# imu_mk1.net
KiCad netlist of a schematic drawn in EAGLE
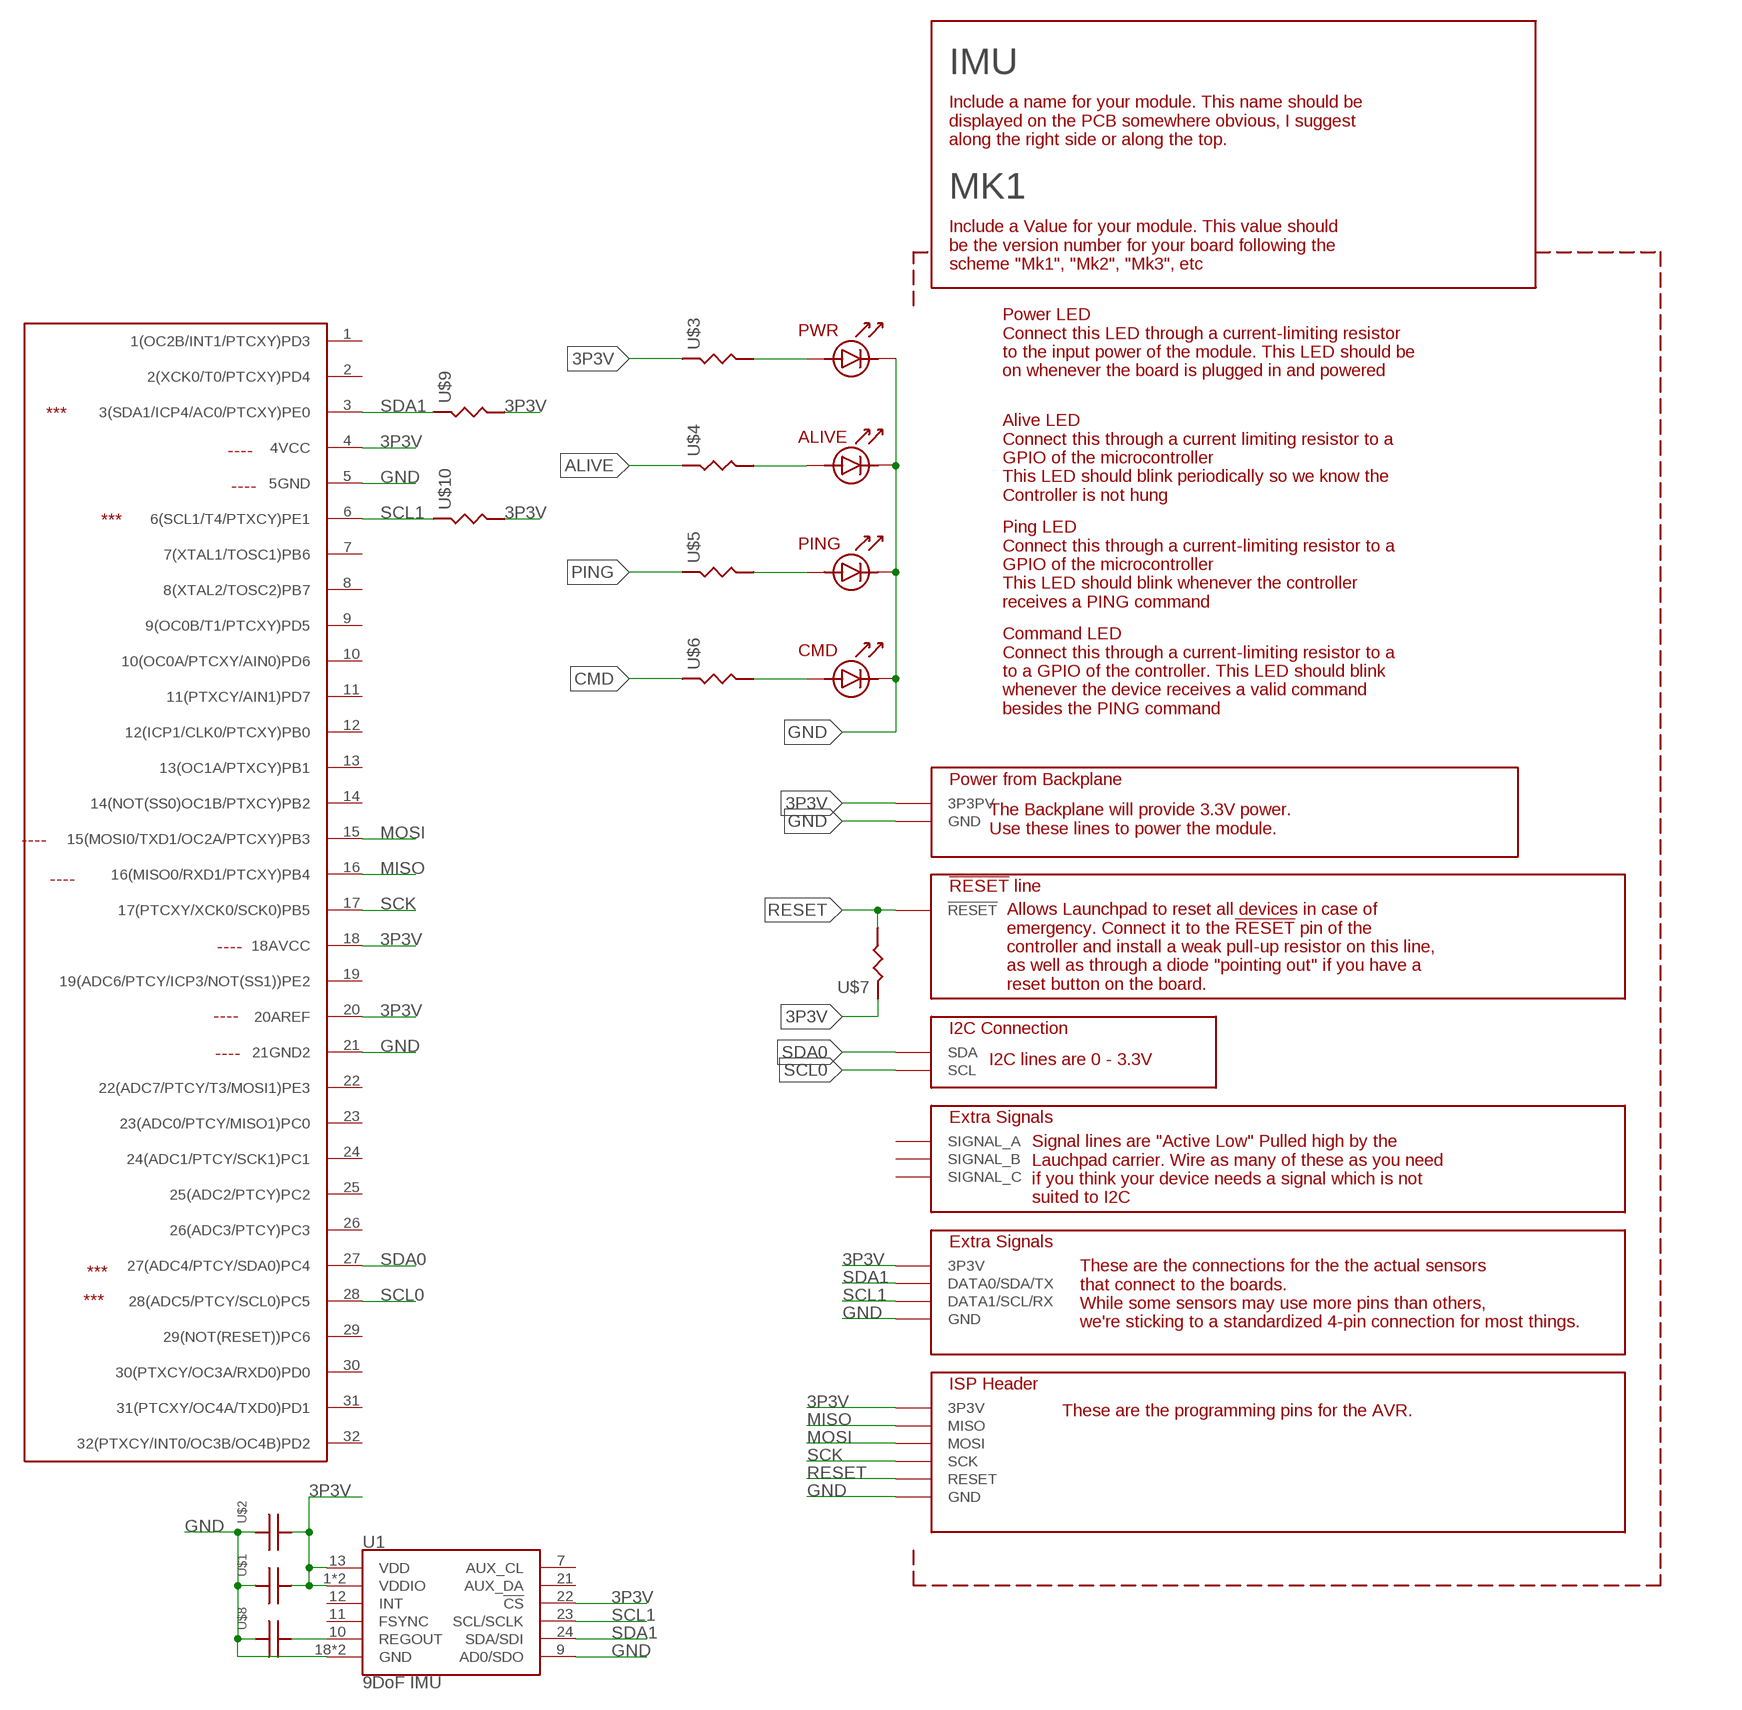
[diagram p0: schematic, sheet 1]

(export (version "E")
  (design (tool "Eeschema 10.0.6"))
  (components
    (comp (ref "IMU")
      (value "MK1")
      (footprint "eagle-import:SENSOR_MODULE_MK1")
      (libsource (lib "eagle-import") (part "SENSOR_MODULE_MK1"))
    )
    (comp (ref "U$1")
      (value "CAPACITOR-UNPOLARIZED0805")
      (footprint "eagle-import:0805_STACKPOLERESISTOR")
      (libsource (lib "eagle-import") (part "CAPACITOR-UNPOLARIZED0805"))
    )
    (comp (ref "U$2")
      (value "CAPACITOR-UNPOLARIZED0805")
      (footprint "eagle-import:0805_STACKPOLERESISTOR")
      (libsource (lib "eagle-import") (part "CAPACITOR-UNPOLARIZED0805"))
    )
    (comp (ref "U$3")
      (value "RESISTOR")
      (footprint "eagle-import:0805_STACKPOLERESISTOR")
      (libsource (lib "eagle-import") (part "RESISTOR"))
    )
    (comp (ref "U$4")
      (value "RESISTOR")
      (footprint "eagle-import:0805_STACKPOLERESISTOR")
      (libsource (lib "eagle-import") (part "RESISTOR"))
    )
    (comp (ref "U$5")
      (value "RESISTOR")
      (footprint "eagle-import:0805_STACKPOLERESISTOR")
      (libsource (lib "eagle-import") (part "RESISTOR"))
    )
    (comp (ref "U$6")
      (value "RESISTOR")
      (footprint "eagle-import:0805_STACKPOLERESISTOR")
      (libsource (lib "eagle-import") (part "RESISTOR"))
    )
    (comp (ref "U$7")
      (value "RESISTOR")
      (footprint "eagle-import:0805_STACKPOLERESISTOR")
      (libsource (lib "eagle-import") (part "RESISTOR"))
    )
    (comp (ref "U$8")
      (value "CAPACITOR-UNPOLARIZED0805")
      (footprint "eagle-import:0805_STACKPOLERESISTOR")
      (libsource (lib "eagle-import") (part "CAPACITOR-UNPOLARIZED0805"))
    )
    (comp (ref "U$9")
      (value "RESISTOR")
      (footprint "eagle-import:0805_STACKPOLERESISTOR")
      (libsource (lib "eagle-import") (part "RESISTOR"))
    )
    (comp (ref "U$10")
      (value "RESISTOR")
      (footprint "eagle-import:0805_STACKPOLERESISTOR")
      (libsource (lib "eagle-import") (part "RESISTOR"))
    )
    (comp (ref "U1")
      (value "9DoF IMU")
      (footprint "eagle-import:QFN24-3X3")
      (libsource (lib "eagle-import") (part "MPU-9250"))
    )
    (comp (ref "U100")
      (value "ATMEGA328PB")
      (footprint "eagle-import:TQFP32-08")
      (libsource (lib "eagle-import") (part "ATMEGA328PB"))
    )
  )
  (nets
    (net (code "1") (name "/MISO") (class "Default")
      (node (ref "IMU") (pin "MISO") (pinfunction "MISO_MISO") (pintype "bidirectional"))
      (node (ref "U100") (pin "16") (pinfunction "16(MISO0/RXD1/PTCXY)PB4_16") (pintype "bidirectional"))
    )
    (net (code "2") (name "/MOSI") (class "Default")
      (node (ref "IMU") (pin "MOSI") (pinfunction "MOSI_MOSI") (pintype "bidirectional"))
      (node (ref "U100") (pin "15") (pinfunction "15(MOSI0/TXD1/OC2A/PTCXY)PB3_15") (pintype "bidirectional"))
    )
    (net (code "3") (name "/SCK") (class "Default")
      (node (ref "IMU") (pin "SCK") (pinfunction "SCK_SCK") (pintype "bidirectional"))
      (node (ref "U100") (pin "17") (pinfunction "17(PTCXY/XCK0/SCK0)PB5_17") (pintype "bidirectional"))
    )
    (net (code "4") (name "/SCL1") (class "Default")
      (node (ref "IMU") (pin "DATA1@1") (pinfunction "DATA1/SCL/RX_DATA1@1") (pintype "bidirectional"))
      (node (ref "IMU") (pin "DATA1@2") (pinfunction "DATA1/SCL/RX_DATA1@2") (pintype "bidirectional"))
      (node (ref "U$10") (pin "P$1") (pinfunction "P$1_P$1") (pintype "bidirectional"))
      (node (ref "U1") (pin "23") (pinfunction "SCL/SCLK_23") (pintype "bidirectional"))
      (node (ref "U100") (pin "6") (pinfunction "6(SCL1/T4/PTXCY)PE1_6") (pintype "bidirectional"))
    )
    (net (code "5") (name "/SDA1") (class "Default")
      (node (ref "IMU") (pin "DATA0@1") (pinfunction "DATA0/SDA/TX_DATA0@1") (pintype "bidirectional"))
      (node (ref "IMU") (pin "DATA0@2") (pinfunction "DATA0/SDA/TX_DATA0@2") (pintype "bidirectional"))
      (node (ref "U$9") (pin "P$1") (pinfunction "P$1_P$1") (pintype "bidirectional"))
      (node (ref "U1") (pin "24") (pinfunction "SDA/SDI_24") (pintype "bidirectional"))
      (node (ref "U100") (pin "3") (pinfunction "3(SDA1/ICP4/AC0/PTCXY)PE0_3") (pintype "bidirectional"))
    )
    (net (code "6") (name "3P3V") (class "Default")
      (node (ref "IMU") (pin "3P3V@1") (pinfunction "3P3PV_3P3V@1") (pintype "bidirectional"))
      (node (ref "IMU") (pin "3P3V@2") (pinfunction "3P3V_3P3V@2") (pintype "bidirectional"))
      (node (ref "IMU") (pin "3P3V@3") (pinfunction "3P3V_3P3V@3") (pintype "bidirectional"))
      (node (ref "IMU") (pin "3P3V@4") (pinfunction "3P3V_3P3V@4") (pintype "bidirectional"))
      (node (ref "U$1") (pin "P$2") (pinfunction "P$2_P$2") (pintype "bidirectional"))
      (node (ref "U$10") (pin "P$2") (pinfunction "P$2_P$2") (pintype "bidirectional"))
      (node (ref "U$2") (pin "P$2") (pinfunction "P$2_P$2") (pintype "bidirectional"))
      (node (ref "U$3") (pin "P$1") (pinfunction "P$1_P$1") (pintype "bidirectional"))
      (node (ref "U$7") (pin "P$1") (pinfunction "P$1_P$1") (pintype "bidirectional"))
      (node (ref "U$9") (pin "P$2") (pinfunction "P$2_P$2") (pintype "bidirectional"))
      (node (ref "U1") (pin "1") (pinfunction "VDDIO_1") (pintype "bidirectional"))
      (node (ref "U1") (pin "13") (pinfunction "VDD_13") (pintype "bidirectional"))
      (node (ref "U1") (pin "22") (pinfunction "~{CS}_22") (pintype "bidirectional"))
      (node (ref "U1") (pin "8") (pinfunction "VDDIO_8") (pintype "bidirectional"))
      (node (ref "U100") (pin "18") (pinfunction "18AVCC_18") (pintype "bidirectional"))
      (node (ref "U100") (pin "20") (pinfunction "20AREF_20") (pintype "bidirectional"))
      (node (ref "U100") (pin "4") (pinfunction "4VCC_4") (pintype "bidirectional"))
    )
    (net (code "7") (name "ALIVE") (class "Default")
      (node (ref "U$4") (pin "P$1") (pinfunction "P$1_P$1") (pintype "bidirectional"))
    )
    (net (code "8") (name "CMD") (class "Default")
      (node (ref "U$6") (pin "P$1") (pinfunction "P$1_P$1") (pintype "bidirectional"))
    )
    (net (code "9") (name "GND") (class "Default")
      (node (ref "IMU") (pin "ALIVELED_CATHODE") (pinfunction "ALIVELED_CATHODE_ALIVELED_CATHODE") (pintype "bidirectional"))
      (node (ref "IMU") (pin "CMDLED_CATHODE") (pinfunction "CMDLED_CATHODE_CMDLED_CATHODE") (pintype "bidirectional"))
      (node (ref "IMU") (pin "GND@1") (pinfunction "GND_GND@1") (pintype "bidirectional"))
      (node (ref "IMU") (pin "GND@2") (pinfunction "GND_GND@2") (pintype "bidirectional"))
      (node (ref "IMU") (pin "GND@3") (pinfunction "GND_GND@3") (pintype "bidirectional"))
      (node (ref "IMU") (pin "GND@4") (pinfunction "GND_GND@4") (pintype "bidirectional"))
      (node (ref "IMU") (pin "PINGLED_CATHODE") (pinfunction "PINGLED_CATHODE_PINGLED_CATHODE") (pintype "bidirectional"))
      (node (ref "IMU") (pin "PWRLED_CATHODE") (pinfunction "PWRLED_CATHODE_PWRLED_CATHODE") (pintype "bidirectional"))
      (node (ref "U$1") (pin "P$1") (pinfunction "P$1_P$1") (pintype "bidirectional"))
      (node (ref "U$2") (pin "P$1") (pinfunction "P$1_P$1") (pintype "bidirectional"))
      (node (ref "U$8") (pin "P$1") (pinfunction "P$1_P$1") (pintype "bidirectional"))
      (node (ref "U1") (pin "18") (pinfunction "GND_18") (pintype "bidirectional"))
      (node (ref "U1") (pin "20") (pinfunction "GND_20") (pintype "bidirectional"))
      (node (ref "U1") (pin "9") (pinfunction "AD0/SDO_9") (pintype "bidirectional"))
      (node (ref "U100") (pin "21") (pinfunction "21GND2_21") (pintype "bidirectional"))
      (node (ref "U100") (pin "5") (pinfunction "5GND_5") (pintype "bidirectional"))
    )
    (net (code "10") (name "Net-(IMU-PadALIVELED_ANODE)") (class "Default")
      (node (ref "IMU") (pin "ALIVELED_ANODE") (pinfunction "ALIVELED_ANODE_ALIVELED_ANODE") (pintype "bidirectional"))
      (node (ref "U$4") (pin "P$2") (pinfunction "P$2_P$2") (pintype "bidirectional"))
    )
    (net (code "11") (name "Net-(IMU-PadCMDLED_ANODE)") (class "Default")
      (node (ref "IMU") (pin "CMDLED_ANODE") (pinfunction "CMDLED_ANODE_CMDLED_ANODE") (pintype "bidirectional"))
      (node (ref "U$6") (pin "P$2") (pinfunction "P$2_P$2") (pintype "bidirectional"))
    )
    (net (code "12") (name "Net-(IMU-PadPINGLED_ANODE)") (class "Default")
      (node (ref "IMU") (pin "PINGLED_ANODE") (pinfunction "PINGLED_ANODE_PINGLED_ANODE") (pintype "bidirectional"))
      (node (ref "U$5") (pin "P$2") (pinfunction "P$2_P$2") (pintype "bidirectional"))
    )
    (net (code "13") (name "Net-(IMU-PadPWRLED_ANODE)") (class "Default")
      (node (ref "IMU") (pin "PWRLED_ANODE") (pinfunction "PWRLED_ANODE_PWRLED_ANODE") (pintype "bidirectional"))
      (node (ref "U$3") (pin "P$2") (pinfunction "P$2_P$2") (pintype "bidirectional"))
    )
    (net (code "14") (name "Net-(U1-REGOUT)") (class "Default")
      (node (ref "U$8") (pin "P$2") (pinfunction "P$2_P$2") (pintype "bidirectional"))
      (node (ref "U1") (pin "10") (pinfunction "REGOUT_10") (pintype "bidirectional"))
    )
    (net (code "15") (name "PING") (class "Default")
      (node (ref "U$5") (pin "P$1") (pinfunction "P$1_P$1") (pintype "bidirectional"))
    )
    (net (code "16") (name "RESET") (class "Default")
      (node (ref "IMU") (pin "RESET@1") (pinfunction "~{RESET}_RESET@1") (pintype "bidirectional"))
      (node (ref "IMU") (pin "RESET@2") (pinfunction "RESET_RESET@2") (pintype "bidirectional"))
      (node (ref "U$7") (pin "P$2") (pinfunction "P$2_P$2") (pintype "bidirectional"))
    )
    (net (code "17") (name "SCL0") (class "Default")
      (node (ref "IMU") (pin "SCL") (pinfunction "SCL_SCL") (pintype "bidirectional"))
      (node (ref "U100") (pin "28") (pinfunction "28(ADC5/PTCY/SCL0)PC5_28") (pintype "bidirectional"))
    )
    (net (code "18") (name "SDA0") (class "Default")
      (node (ref "IMU") (pin "SDA") (pinfunction "SDA_SDA") (pintype "bidirectional"))
      (node (ref "U100") (pin "27") (pinfunction "27(ADC4/PTCY/SDA0)PC4_27") (pintype "bidirectional"))
    )
    (net (code "19") (name "unconnected-(IMU-SIGNAL_A-PadA)") (class "Default")
      (node (ref "IMU") (pin "A") (pinfunction "SIGNAL_A_A") (pintype "bidirectional"))
    )
    (net (code "20") (name "unconnected-(IMU-SIGNAL_B-PadB)") (class "Default")
      (node (ref "IMU") (pin "B") (pinfunction "SIGNAL_B_B") (pintype "bidirectional"))
    )
    (net (code "21") (name "unconnected-(IMU-SIGNAL_C-PadC)") (class "Default")
      (node (ref "IMU") (pin "C") (pinfunction "SIGNAL_C_C") (pintype "bidirectional"))
    )
    (net (code "22") (name "unconnected-(U1-AUX_CL-Pad7)") (class "Default")
      (node (ref "U1") (pin "7") (pinfunction "AUX_CL_7") (pintype "bidirectional"))
    )
    (net (code "23") (name "unconnected-(U1-AUX_DA-Pad21)") (class "Default")
      (node (ref "U1") (pin "21") (pinfunction "AUX_DA_21") (pintype "bidirectional"))
    )
    (net (code "24") (name "unconnected-(U1-FSYNC-Pad11)") (class "Default")
      (node (ref "U1") (pin "11") (pinfunction "FSYNC_11") (pintype "bidirectional"))
    )
    (net (code "25") (name "unconnected-(U1-INT-Pad12)") (class "Default")
      (node (ref "U1") (pin "12") (pinfunction "INT_12") (pintype "bidirectional"))
    )
    (net (code "26") (name "unconnected-(U100-1(OC2B{slash}INT1{slash}PTCXY)PD3-Pad1)") (class "Default")
      (node (ref "U100") (pin "1") (pinfunction "1(OC2B/INT1/PTCXY)PD3_1") (pintype "bidirectional"))
    )
    (net (code "27") (name "unconnected-(U100-2(XCK0{slash}T0{slash}PTCXY)PD4-Pad2)") (class "Default")
      (node (ref "U100") (pin "2") (pinfunction "2(XCK0/T0/PTCXY)PD4_2") (pintype "bidirectional"))
    )
    (net (code "28") (name "unconnected-(U100-7(XTAL1{slash}TOSC1)PB6-Pad7)") (class "Default")
      (node (ref "U100") (pin "7") (pinfunction "7(XTAL1/TOSC1)PB6_7") (pintype "bidirectional"))
    )
    (net (code "29") (name "unconnected-(U100-8(XTAL2{slash}TOSC2)PB7-Pad8)") (class "Default")
      (node (ref "U100") (pin "8") (pinfunction "8(XTAL2/TOSC2)PB7_8") (pintype "bidirectional"))
    )
    (net (code "30") (name "unconnected-(U100-9(OC0B{slash}T1{slash}PTCXY)PD5-Pad9)") (class "Default")
      (node (ref "U100") (pin "9") (pinfunction "9(OC0B/T1/PTCXY)PD5_9") (pintype "bidirectional"))
    )
    (net (code "31") (name "unconnected-(U100-10(OC0A{slash}PTCXY{slash}AIN0)PD6-Pad10)") (class "Default")
      (node (ref "U100") (pin "10") (pinfunction "10(OC0A/PTCXY/AIN0)PD6_10") (pintype "bidirectional"))
    )
    (net (code "32") (name "unconnected-(U100-11(PTXCY{slash}AIN1)PD7-Pad11)") (class "Default")
      (node (ref "U100") (pin "11") (pinfunction "11(PTXCY/AIN1)PD7_11") (pintype "bidirectional"))
    )
    (net (code "33") (name "unconnected-(U100-12(ICP1{slash}CLK0{slash}PTCXY)PB0-Pad12)") (class "Default")
      (node (ref "U100") (pin "12") (pinfunction "12(ICP1/CLK0/PTCXY)PB0_12") (pintype "bidirectional"))
    )
    (net (code "34") (name "unconnected-(U100-13(OC1A{slash}PTXCY)PB1-Pad13)") (class "Default")
      (node (ref "U100") (pin "13") (pinfunction "13(OC1A/PTXCY)PB1_13") (pintype "bidirectional"))
    )
    (net (code "35") (name "unconnected-(U100-14(NOT(SS0)OC1B{slash}PTXCY)PB2-Pad14)") (class "Default")
      (node (ref "U100") (pin "14") (pinfunction "14(NOT(SS0)OC1B/PTXCY)PB2_14") (pintype "bidirectional"))
    )
    (net (code "36") (name "unconnected-(U100-19(ADC6{slash}PTCY{slash}ICP3{slash}NOT(SS1))PE2-Pad19)") (class "Default")
      (node (ref "U100") (pin "19") (pinfunction "19(ADC6/PTCY/ICP3/NOT(SS1))PE2_19") (pintype "bidirectional"))
    )
    (net (code "37") (name "unconnected-(U100-22(ADC7{slash}PTCY{slash}T3{slash}MOSI1)PE3-Pad22)") (class "Default")
      (node (ref "U100") (pin "22") (pinfunction "22(ADC7/PTCY/T3/MOSI1)PE3_22") (pintype "bidirectional"))
    )
    (net (code "38") (name "unconnected-(U100-23(ADC0{slash}PTCY{slash}MISO1)PC0-Pad23)") (class "Default")
      (node (ref "U100") (pin "23") (pinfunction "23(ADC0/PTCY/MISO1)PC0_23") (pintype "bidirectional"))
    )
    (net (code "39") (name "unconnected-(U100-24(ADC1{slash}PTCY{slash}SCK1)PC1-Pad24)") (class "Default")
      (node (ref "U100") (pin "24") (pinfunction "24(ADC1/PTCY/SCK1)PC1_24") (pintype "bidirectional"))
    )
    (net (code "40") (name "unconnected-(U100-25(ADC2{slash}PTCY)PC2-Pad25)") (class "Default")
      (node (ref "U100") (pin "25") (pinfunction "25(ADC2/PTCY)PC2_25") (pintype "bidirectional"))
    )
    (net (code "41") (name "unconnected-(U100-26(ADC3{slash}PTCY)PC3-Pad26)") (class "Default")
      (node (ref "U100") (pin "26") (pinfunction "26(ADC3/PTCY)PC3_26") (pintype "bidirectional"))
    )
    (net (code "42") (name "unconnected-(U100-29(NOT(RESET))PC6-Pad29)") (class "Default")
      (node (ref "U100") (pin "29") (pinfunction "29(NOT(RESET))PC6_29") (pintype "bidirectional"))
    )
    (net (code "43") (name "unconnected-(U100-30(PTXCY{slash}OC3A{slash}RXD0)PD0-Pad30)") (class "Default")
      (node (ref "U100") (pin "30") (pinfunction "30(PTXCY/OC3A/RXD0)PD0_30") (pintype "bidirectional"))
    )
    (net (code "44") (name "unconnected-(U100-31(PTCXY{slash}OC4A{slash}TXD0)PD1-Pad31)") (class "Default")
      (node (ref "U100") (pin "31") (pinfunction "31(PTCXY/OC4A/TXD0)PD1_31") (pintype "bidirectional"))
    )
    (net (code "45") (name "unconnected-(U100-32(PTXCY{slash}INT0{slash}OC3B{slash}OC4B)PD2-Pad32)") (class "Default")
      (node (ref "U100") (pin "32") (pinfunction "32(PTXCY/INT0/OC3B/OC4B)PD2_32") (pintype "bidirectional"))
    )
  )
)
